# nesa-3_0.net
KiCad netlist of a schematic drawn in EAGLE
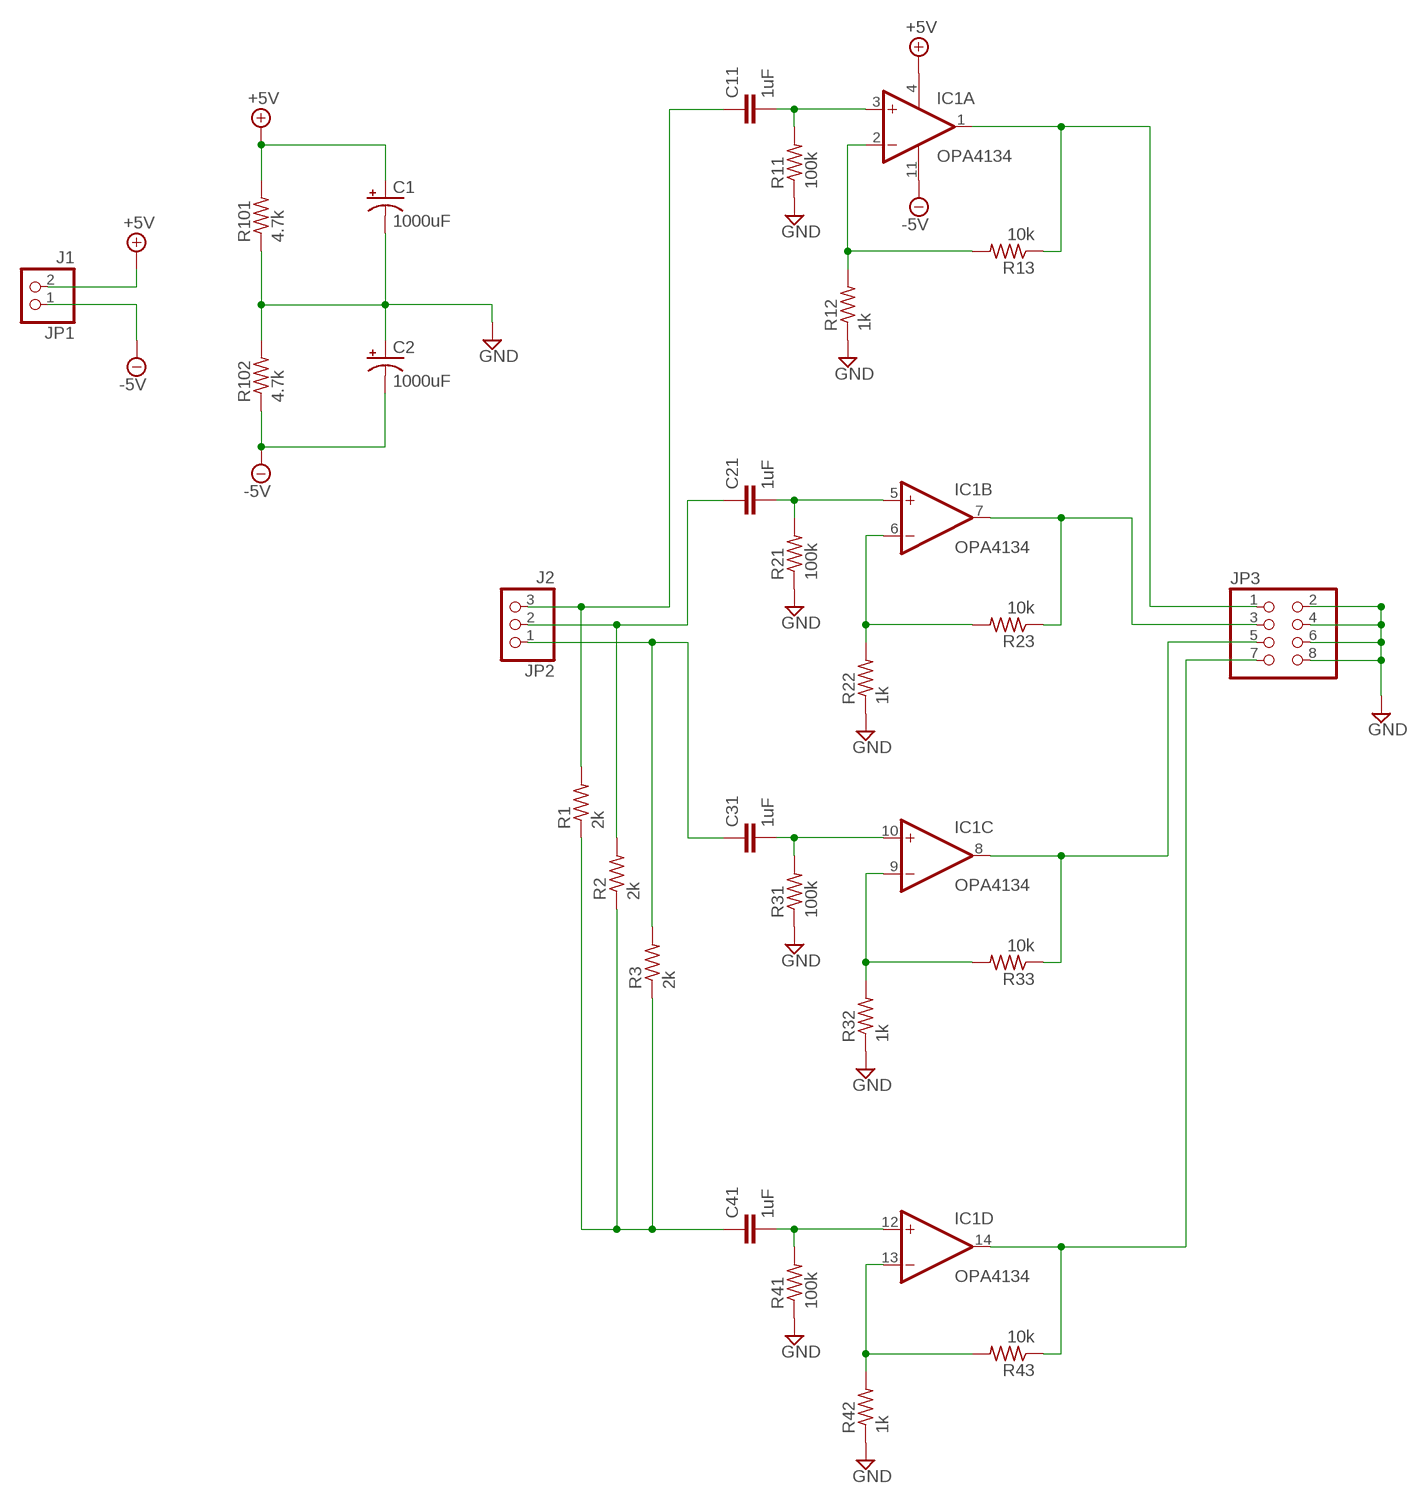
[diagram p0: schematic, sheet 1]

(export (version "E")
  (design (tool "Eeschema 10.0.6"))
  (components
    (comp (ref "C1")
      (value "1000uF")
      (footprint "eagle-import:E3,5-10")
      (libsource (lib "eagle-import") (part "CPOL-USE3.5-10"))
    )
    (comp (ref "C2")
      (value "1000uF")
      (footprint "eagle-import:E3,5-10")
      (libsource (lib "eagle-import") (part "CPOL-USE3.5-10"))
    )
    (comp (ref "C11")
      (value "1uF")
      (footprint "eagle-import:C5B7.2")
      (libsource (lib "eagle-import") (part "C5/7.2"))
    )
    (comp (ref "C21")
      (value "1uF")
      (footprint "eagle-import:C5B7.2")
      (libsource (lib "eagle-import") (part "C5/7.2"))
    )
    (comp (ref "C31")
      (value "1uF")
      (footprint "eagle-import:C5B7.2")
      (libsource (lib "eagle-import") (part "C5/7.2"))
    )
    (comp (ref "C41")
      (value "1uF")
      (footprint "eagle-import:C5B7.2")
      (libsource (lib "eagle-import") (part "C5/7.2"))
    )
    (comp (ref "IC1")
      (value "OPA4134")
      (footprint "eagle-import:DIL14")
      (libsource (lib "eagle-import") (part "MCP604P"))
    )
    (comp (ref "JP1")
      (value "J1")
      (footprint "eagle-import:1X02")
      (libsource (lib "eagle-import") (part "PINHD-1X2"))
    )
    (comp (ref "JP2")
      (value "J2")
      (footprint "eagle-import:1X03")
      (libsource (lib "eagle-import") (part "PINHD-1X3"))
    )
    (comp (ref "JP3")
      (value "PINHD-2X4")
      (footprint "eagle-import:2X04")
      (libsource (lib "eagle-import") (part "PINHD-2X4"))
    )
    (comp (ref "R1")
      (value "2k")
      (footprint "eagle-import:0204_7")
      (libsource (lib "eagle-import") (part "R-US_0204/7"))
    )
    (comp (ref "R2")
      (value "2k")
      (footprint "eagle-import:0204_7")
      (libsource (lib "eagle-import") (part "R-US_0204/7"))
    )
    (comp (ref "R3")
      (value "2k")
      (footprint "eagle-import:0204_7")
      (libsource (lib "eagle-import") (part "R-US_0204/7"))
    )
    (comp (ref "R11")
      (value "100k")
      (footprint "eagle-import:0204_7")
      (libsource (lib "eagle-import") (part "R-US_0204/7"))
    )
    (comp (ref "R12")
      (value "1k")
      (footprint "eagle-import:0204_7")
      (libsource (lib "eagle-import") (part "R-US_0204/7"))
    )
    (comp (ref "R13")
      (value "10k")
      (footprint "eagle-import:0204_7")
      (libsource (lib "eagle-import") (part "R-US_0204/7"))
    )
    (comp (ref "R21")
      (value "100k")
      (footprint "eagle-import:0204_7")
      (libsource (lib "eagle-import") (part "R-US_0204/7"))
    )
    (comp (ref "R22")
      (value "1k")
      (footprint "eagle-import:0204_7")
      (libsource (lib "eagle-import") (part "R-US_0204/7"))
    )
    (comp (ref "R23")
      (value "10k")
      (footprint "eagle-import:0204_7")
      (libsource (lib "eagle-import") (part "R-US_0204/7"))
    )
    (comp (ref "R31")
      (value "100k")
      (footprint "eagle-import:0204_7")
      (libsource (lib "eagle-import") (part "R-US_0204/7"))
    )
    (comp (ref "R32")
      (value "1k")
      (footprint "eagle-import:0204_7")
      (libsource (lib "eagle-import") (part "R-US_0204/7"))
    )
    (comp (ref "R33")
      (value "10k")
      (footprint "eagle-import:0204_7")
      (libsource (lib "eagle-import") (part "R-US_0204/7"))
    )
    (comp (ref "R41")
      (value "100k")
      (footprint "eagle-import:0204_7")
      (libsource (lib "eagle-import") (part "R-US_0204/7"))
    )
    (comp (ref "R42")
      (value "1k")
      (footprint "eagle-import:0204_7")
      (libsource (lib "eagle-import") (part "R-US_0204/7"))
    )
    (comp (ref "R43")
      (value "10k")
      (footprint "eagle-import:0204_7")
      (libsource (lib "eagle-import") (part "R-US_0204/7"))
    )
    (comp (ref "R101")
      (value "4.7k")
      (footprint "eagle-import:0204_7")
      (libsource (lib "eagle-import") (part "R-US_0204/7"))
    )
    (comp (ref "R102")
      (value "4.7k")
      (footprint "eagle-import:0204_7")
      (libsource (lib "eagle-import") (part "R-US_0204/7"))
    )
  )
  (nets
    (net (code "1") (name "+5V") (class "Default")
      (node (ref "C1") (pin "+") (pinfunction "+_+") (pintype "passive"))
      (node (ref "IC1") (pin "4") (pinfunction "V+_4") (pintype "power_in"))
      (node (ref "JP1") (pin "2") (pinfunction "2_2") (pintype "passive"))
      (node (ref "R101") (pin "2") (pinfunction "2_2") (pintype "passive"))
    )
    (net (code "2") (name "-5V") (class "Default")
      (node (ref "C2") (pin "-") (pinfunction "-_-") (pintype "passive"))
      (node (ref "IC1") (pin "11") (pinfunction "V-_11") (pintype "power_in"))
      (node (ref "JP1") (pin "1") (pinfunction "1_1") (pintype "passive"))
      (node (ref "R102") (pin "1") (pinfunction "1_1") (pintype "passive"))
    )
    (net (code "3") (name "GND") (class "Default")
      (node (ref "C1") (pin "-") (pinfunction "-_-") (pintype "passive"))
      (node (ref "C2") (pin "+") (pinfunction "+_+") (pintype "passive"))
      (node (ref "JP3") (pin "2") (pinfunction "2_2") (pintype "passive"))
      (node (ref "JP3") (pin "4") (pinfunction "4_4") (pintype "passive"))
      (node (ref "JP3") (pin "6") (pinfunction "6_6") (pintype "passive"))
      (node (ref "JP3") (pin "8") (pinfunction "8_8") (pintype "passive"))
      (node (ref "R101") (pin "1") (pinfunction "1_1") (pintype "passive"))
      (node (ref "R102") (pin "2") (pinfunction "2_2") (pintype "passive"))
      (node (ref "R11") (pin "1") (pinfunction "1_1") (pintype "passive"))
      (node (ref "R12") (pin "1") (pinfunction "1_1") (pintype "passive"))
      (node (ref "R21") (pin "1") (pinfunction "1_1") (pintype "passive"))
      (node (ref "R22") (pin "1") (pinfunction "1_1") (pintype "passive"))
      (node (ref "R31") (pin "1") (pinfunction "1_1") (pintype "passive"))
      (node (ref "R32") (pin "1") (pinfunction "1_1") (pintype "passive"))
      (node (ref "R41") (pin "1") (pinfunction "1_1") (pintype "passive"))
      (node (ref "R42") (pin "1") (pinfunction "1_1") (pintype "passive"))
    )
    (net (code "4") (name "Net-(C11-Pad1)") (class "Default")
      (node (ref "C11") (pin "1") (pinfunction "1_1") (pintype "passive"))
      (node (ref "JP2") (pin "3") (pinfunction "3_3") (pintype "passive"))
      (node (ref "R1") (pin "2") (pinfunction "2_2") (pintype "passive"))
    )
    (net (code "5") (name "Net-(C21-Pad1)") (class "Default")
      (node (ref "C21") (pin "1") (pinfunction "1_1") (pintype "passive"))
      (node (ref "JP2") (pin "2") (pinfunction "2_2") (pintype "passive"))
      (node (ref "R2") (pin "2") (pinfunction "2_2") (pintype "passive"))
    )
    (net (code "6") (name "Net-(C31-Pad1)") (class "Default")
      (node (ref "C31") (pin "1") (pinfunction "1_1") (pintype "passive"))
      (node (ref "JP2") (pin "1") (pinfunction "1_1") (pintype "passive"))
      (node (ref "R3") (pin "2") (pinfunction "2_2") (pintype "passive"))
    )
    (net (code "7") (name "Net-(C41-Pad1)") (class "Default")
      (node (ref "C41") (pin "1") (pinfunction "1_1") (pintype "passive"))
      (node (ref "R1") (pin "1") (pinfunction "1_1") (pintype "passive"))
      (node (ref "R2") (pin "1") (pinfunction "1_1") (pintype "passive"))
      (node (ref "R3") (pin "1") (pinfunction "1_1") (pintype "passive"))
    )
    (net (code "8") (name "Net-(IC1A-+IN)") (class "Default")
      (node (ref "C11") (pin "2") (pinfunction "2_2") (pintype "passive"))
      (node (ref "IC1") (pin "3") (pinfunction "+IN_3") (pintype "input"))
      (node (ref "R11") (pin "2") (pinfunction "2_2") (pintype "passive"))
    )
    (net (code "9") (name "Net-(IC1A--IN)") (class "Default")
      (node (ref "IC1") (pin "2") (pinfunction "-IN_2") (pintype "input"))
      (node (ref "R12") (pin "2") (pinfunction "2_2") (pintype "passive"))
      (node (ref "R13") (pin "2") (pinfunction "2_2") (pintype "passive"))
    )
    (net (code "10") (name "Net-(IC1A-OUT)") (class "Default")
      (node (ref "IC1") (pin "1") (pinfunction "OUT_1") (pintype "output"))
      (node (ref "JP3") (pin "1") (pinfunction "1_1") (pintype "passive"))
      (node (ref "R13") (pin "1") (pinfunction "1_1") (pintype "passive"))
    )
    (net (code "11") (name "Net-(IC1B-+IN)") (class "Default")
      (node (ref "C21") (pin "2") (pinfunction "2_2") (pintype "passive"))
      (node (ref "IC1") (pin "5") (pinfunction "+IN_5") (pintype "input"))
      (node (ref "R21") (pin "2") (pinfunction "2_2") (pintype "passive"))
    )
    (net (code "12") (name "Net-(IC1B--IN)") (class "Default")
      (node (ref "IC1") (pin "6") (pinfunction "-IN_6") (pintype "input"))
      (node (ref "R22") (pin "2") (pinfunction "2_2") (pintype "passive"))
      (node (ref "R23") (pin "2") (pinfunction "2_2") (pintype "passive"))
    )
    (net (code "13") (name "Net-(IC1B-OUT)") (class "Default")
      (node (ref "IC1") (pin "7") (pinfunction "OUT_7") (pintype "output"))
      (node (ref "JP3") (pin "3") (pinfunction "3_3") (pintype "passive"))
      (node (ref "R23") (pin "1") (pinfunction "1_1") (pintype "passive"))
    )
    (net (code "14") (name "Net-(IC1C-+IN)") (class "Default")
      (node (ref "C31") (pin "2") (pinfunction "2_2") (pintype "passive"))
      (node (ref "IC1") (pin "10") (pinfunction "+IN_10") (pintype "input"))
      (node (ref "R31") (pin "2") (pinfunction "2_2") (pintype "passive"))
    )
    (net (code "15") (name "Net-(IC1C--IN)") (class "Default")
      (node (ref "IC1") (pin "9") (pinfunction "-IN_9") (pintype "input"))
      (node (ref "R32") (pin "2") (pinfunction "2_2") (pintype "passive"))
      (node (ref "R33") (pin "2") (pinfunction "2_2") (pintype "passive"))
    )
    (net (code "16") (name "Net-(IC1C-OUT)") (class "Default")
      (node (ref "IC1") (pin "8") (pinfunction "OUT_8") (pintype "output"))
      (node (ref "JP3") (pin "5") (pinfunction "5_5") (pintype "passive"))
      (node (ref "R33") (pin "1") (pinfunction "1_1") (pintype "passive"))
    )
    (net (code "17") (name "Net-(IC1D-+IN)") (class "Default")
      (node (ref "C41") (pin "2") (pinfunction "2_2") (pintype "passive"))
      (node (ref "IC1") (pin "12") (pinfunction "+IN_12") (pintype "input"))
      (node (ref "R41") (pin "2") (pinfunction "2_2") (pintype "passive"))
    )
    (net (code "18") (name "Net-(IC1D--IN)") (class "Default")
      (node (ref "IC1") (pin "13") (pinfunction "-IN_13") (pintype "input"))
      (node (ref "R42") (pin "2") (pinfunction "2_2") (pintype "passive"))
      (node (ref "R43") (pin "2") (pinfunction "2_2") (pintype "passive"))
    )
    (net (code "19") (name "Net-(IC1D-OUT)") (class "Default")
      (node (ref "IC1") (pin "14") (pinfunction "OUT_14") (pintype "output"))
      (node (ref "JP3") (pin "7") (pinfunction "7_7") (pintype "passive"))
      (node (ref "R43") (pin "1") (pinfunction "1_1") (pintype "passive"))
    )
  )
)
